# RTC.net
KiCad netlist of a schematic drawn in Altium Designer
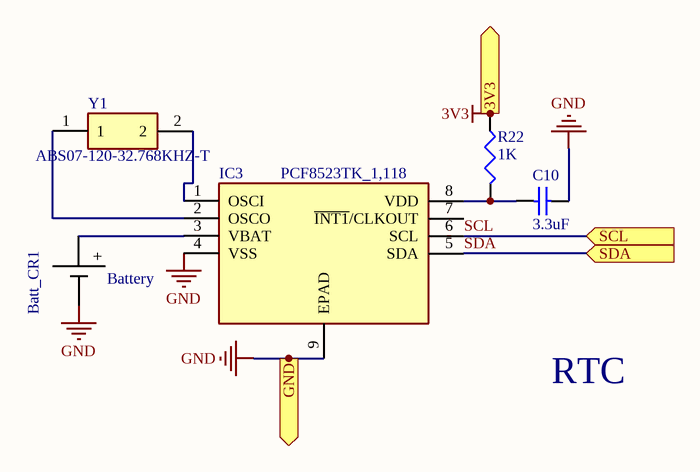
[diagram p0: RTC.SchDoc]

(export (version "E")
  (design (tool "Eeschema 10.0.6"))
  (components
    (comp (ref "Batt_CR1")
      (value "Battery")
      (footprint "Battery 1220")
      (description "Undefined or Miscellaneous")
      (fields (field (name "MOUSER PART NUMBER") "534-1074") (field (name "MANUFACTURER_PART_NUMBER") "1074"))
      (libsource (lib "SamacSys") (part "1074"))
    )
    (comp (ref "C10")
      (value "3.3uF")
      (footprint "1608[0603]")
      (description "Capacitor (Semiconductor SIM Model)")
      (fields (field (name "PUBLISHER") "Altium Limited"))
      (libsource (lib "Miscellaneous Devices") (part "Cap Semi"))
    )
    (comp (ref "IC3")
      (value "PCF8523TK_1,118")
      (footprint "SamacSys:SON80P400X400X100-9N")
      (description "Integrated Circuit")
      (fields
        (field (name "MANUFACTURER_PART_NUMBER") "PCF8523TK/1,118")
        (field (name "MOUSER PART NUMBER") "771-PCF8523TK/1118")
      )
      (libsource (lib "SamacSys") (part "PCF8523TK_1,118"))
    )
    (comp (ref "R22")
      (value "1K")
      (footprint "J1-0603")
      (description "Resistor")
      (fields (field (name "PUBLISHER") "Altium Limited"))
      (libsource (lib "Miscellaneous Devices") (part "Res3"))
    )
    (comp (ref "Y1")
      (value "ABS07-120-32.768KHZ-T")
      (footprint "SamacSys:ABS-07")
      (description "Crystal or Oscillator")
      (fields
        (field (name "MOUSER PART NUMBER") "815-ABS0712032.768KT")
        (field (name "RS PART NUMBER") "1712688P")
      )
      (libsource (lib "SamacSys") (part "ABS07-120-32.768KHZ-T"))
    )
  )
  (nets
    (net (code "1") (name "/SCL") (class "Default")
      (node (ref "IC3") (pin "6") (pinfunction "SCL_6") (pintype "passive"))
    )
    (net (code "2") (name "/SDA") (class "Default")
      (node (ref "IC3") (pin "5") (pinfunction "SDA_5") (pintype "passive"))
    )
    (net (code "3") (name "3V3") (class "Default")
      (node (ref "R22") (pin "1") (pinfunction "1_1") (pintype "passive"))
    )
    (net (code "4") (name "GND") (class "Default")
      (node (ref "Batt_CR1") (pin "2") (pinfunction "-_2") (pintype "passive"))
      (node (ref "C10") (pin "2") (pinfunction "2_2") (pintype "passive"))
      (node (ref "IC3") (pin "4") (pinfunction "VSS_4") (pintype "passive"))
      (node (ref "IC3") (pin "9") (pinfunction "EPAD_9") (pintype "passive"))
    )
    (net (code "5") (name "Net-(Batt_CR1-+)") (class "Default")
      (node (ref "Batt_CR1") (pin "1") (pinfunction "+_1") (pintype "passive"))
      (node (ref "IC3") (pin "3") (pinfunction "VBAT_3") (pintype "passive"))
    )
    (net (code "6") (name "Net-(IC3-OSCI)") (class "Default")
      (node (ref "IC3") (pin "1") (pinfunction "OSCI_1") (pintype "passive"))
      (node (ref "Y1") (pin "2") (pinfunction "2_2") (pintype "passive"))
    )
    (net (code "7") (name "Net-(IC3-OSCO)") (class "Default")
      (node (ref "IC3") (pin "2") (pinfunction "OSCO_2") (pintype "passive"))
      (node (ref "Y1") (pin "1") (pinfunction "1_1") (pintype "passive"))
    )
    (net (code "8") (name "Net-(IC3-VDD)") (class "Default")
      (node (ref "C10") (pin "1") (pinfunction "1_1") (pintype "passive"))
      (node (ref "IC3") (pin "8") (pinfunction "VDD_8") (pintype "passive"))
      (node (ref "R22") (pin "2") (pinfunction "2_2") (pintype "passive"))
    )
    (net (code "9") (name "unconnected-(IC3-~{INT1}{slash}CLKOUT-Pad7)") (class "Default")
      (node (ref "IC3") (pin "7") (pinfunction "~{INT1}/CLKOUT_7") (pintype "passive"))
    )
  )
)
